# handle.net
KiCad netlist of a schematic drawn in EAGLE
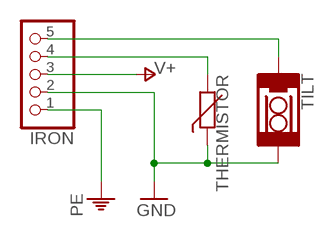
[diagram p0: schematic, sheet 1]

(export (version "E")
  (design (tool "Eeschema 10.0.6"))
  (components
    (comp (ref "IRON")
      (value "PINHD-1X5")
      (footprint "eagle-import:1X05")
      (libsource (lib "eagle-import") (part "PINHD-1X5"))
    )
    (comp (ref "THERMISTOR")
      (value "THERMISTOR_R-2,5")
      (footprint "eagle-import:RS-2,5")
      (libsource (lib "eagle-import") (part "THERMISTOR_R-2,5"))
    )
    (comp (ref "TILT")
      (value "SQ-SEN-200")
      (footprint "eagle-import:SQ-SEN-200")
      (libsource (lib "eagle-import") (part "SQ-SEN-200"))
    )
  )
  (nets
    (net (code "1") (name "GND") (class "Default")
      (node (ref "IRON") (pin "2") (pinfunction "2_2") (pintype "passive"))
      (node (ref "THERMISTOR") (pin "1") (pinfunction "1_1") (pintype "passive"))
      (node (ref "TILT") (pin "2") (pinfunction "2_2") (pintype "passive"))
    )
    (net (code "2") (name "Net-(IRON-Pad4)") (class "Default")
      (node (ref "IRON") (pin "4") (pinfunction "4_4") (pintype "passive"))
      (node (ref "THERMISTOR") (pin "2") (pinfunction "2_2") (pintype "passive"))
    )
    (net (code "3") (name "Net-(IRON-Pad5)") (class "Default")
      (node (ref "IRON") (pin "5") (pinfunction "5_5") (pintype "passive"))
      (node (ref "TILT") (pin "1") (pinfunction "1_1") (pintype "passive"))
    )
    (net (code "4") (name "PE") (class "Default")
      (node (ref "IRON") (pin "1") (pinfunction "1_1") (pintype "passive"))
    )
    (net (code "5") (name "V+") (class "Default")
      (node (ref "IRON") (pin "3") (pinfunction "3_3") (pintype "passive"))
    )
  )
)
